# Sound.net
KiCad netlist of a schematic drawn in Altium Designer
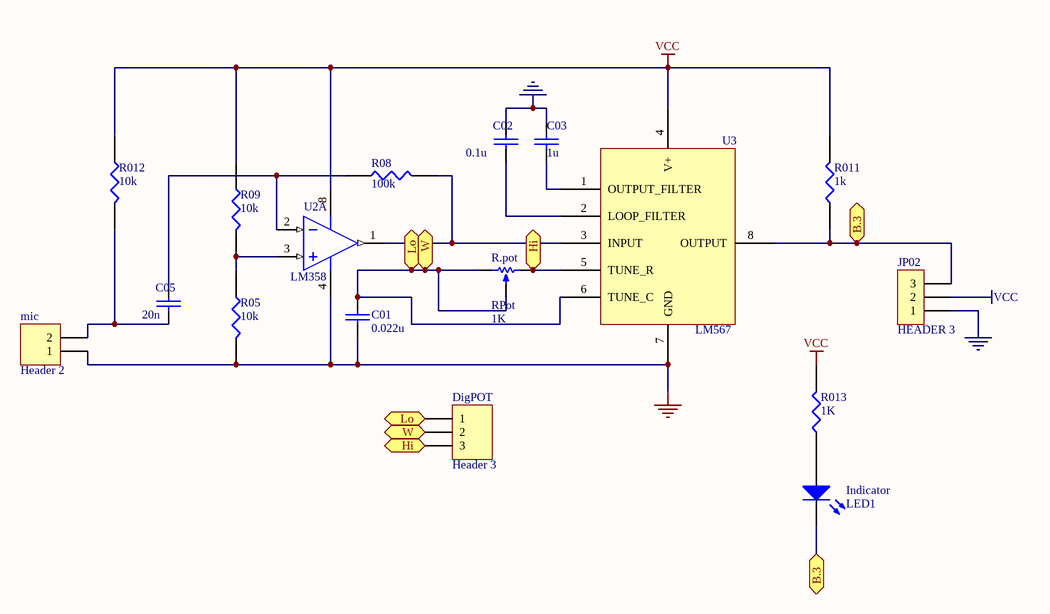
[diagram p0: Sound.SchDoc]

(export (version "E")
  (design (tool "Eeschema 10.0.6"))
  (components
    (comp (ref "C01")
      (value "0.022u")
      (footprint "RAD-0.1")
      (description "Capacitor")
      (libsource (lib "*") (part "CAP"))
    )
    (comp (ref "C02")
      (value "0.1u")
      (footprint "RAD-0.1")
      (description "Capacitor")
      (libsource (lib "*") (part "CAP"))
    )
    (comp (ref "C03")
      (value "1u")
      (footprint "RAD-0.1")
      (description "Capacitor")
      (libsource (lib "*") (part "CAP"))
    )
    (comp (ref "C05")
      (value "20n")
      (footprint "RAD-0.1")
      (description "Capacitor")
      (libsource (lib "*") (part "CAP"))
    )
    (comp (ref "DigPOT")
      (value "Header 3")
      (footprint "HDR1X3")
      (description "Header, 3-Pin")
      (fields (field (name "PUBLISHER") "Altium Limited"))
      (libsource (lib "Miscellaneous Connectors") (part "Header 3"))
    )
    (comp (ref "Indicator")
      (value "LED1")
      (footprint "LED-1")
      (description "Typical RED GaAs LED")
      (fields (field (name "PUBLISHER") "Altium Limited"))
      (libsource (lib "Miscellaneous Devices") (part "LED1"))
    )
    (comp (ref "JP02")
      (value "HEADER 3")
      (footprint "HDR1X3")
      (description "Connector")
      (libsource (lib "*") (part "CON3"))
    )
    (comp (ref "mic")
      (value "Header 2")
      (footprint "HDR1X2")
      (description "Header, 2-Pin")
      (fields (field (name "PUBLISHER") "Altium Limited"))
      (libsource (lib "Miscellaneous Connectors") (part "Header 2"))
    )
    (comp (ref "R.pot")
      (value "RPot")
      (footprint "VR5")
      (description "Potentiometer")
      (fields (field (name "ALTIUM_VALUE") "1K") (field (name "PUBLISHER") "Altium Limited"))
      (libsource (lib "Miscellaneous Devices") (part "RPot"))
    )
    (comp (ref "R05") (value "10k") (footprint "AXIAL-0.3") (libsource (lib "*") (part "RES1")))
    (comp (ref "R08") (value "100k") (footprint "AXIAL-0.3") (libsource (lib "*") (part "RES1")))
    (comp (ref "R09") (value "10k") (footprint "AXIAL-0.3") (libsource (lib "*") (part "RES1")))
    (comp (ref "R011") (value "1k") (footprint "AXIAL-0.3") (libsource (lib "*") (part "RES1")))
    (comp (ref "R012") (value "10k") (footprint "AXIAL-0.3") (libsource (lib "*") (part "RES1")))
    (comp (ref "R013") (value "1K") (footprint "AXIAL-0.3") (libsource (lib "*") (part "RES1")))
    (comp (ref "U2")
      (value "LM358")
      (footprint "DIP-8")
      (description "Fast Settling Dual Operational Amplifier")
      (libsource (lib "*") (part "LM358"))
    )
    (comp (ref "U3") (value "LM567") (footprint "DIP-8") (libsource (lib "*") (part "LM567")))
  )
  (nets
    (net (code "1") (name "/B.3") (class "Default")
      (node (ref "Indicator") (pin "2") (pinfunction "K_2") (pintype "passive"))
      (node (ref "JP02") (pin "3") (pinfunction "3_3") (pintype "passive"))
      (node (ref "R011") (pin "1") (pinfunction "1_1") (pintype "passive"))
      (node (ref "U3") (pin "8") (pinfunction "OUTPUT_8") (pintype "passive"))
    )
    (net (code "2") (name "/Hi") (class "Default")
      (node (ref "DigPOT") (pin "3") (pinfunction "3_3") (pintype "passive"))
      (node (ref "R.pot") (pin "2") (pinfunction "BOT_2") (pintype "passive"))
      (node (ref "U3") (pin "5") (pinfunction "TUNE_R_5") (pintype "passive"))
    )
    (net (code "3") (name "/Lo") (class "Default")
      (node (ref "C01") (pin "1") (pinfunction "1_1") (pintype "passive"))
      (node (ref "DigPOT") (pin "1") (pinfunction "1_1") (pintype "passive"))
      (node (ref "DigPOT") (pin "2") (pinfunction "2_2") (pintype "passive"))
      (node (ref "R.pot") (pin "1") (pinfunction "TOP_1") (pintype "passive"))
      (node (ref "R.pot") (pin "3") (pinfunction "TAP_3") (pintype "passive"))
      (node (ref "U3") (pin "6") (pinfunction "TUNE_C_6") (pintype "passive"))
    )
    (net (code "4") (name "GND") (class "Default")
      (node (ref "C01") (pin "2") (pinfunction "2_2") (pintype "passive"))
      (node (ref "C02") (pin "1") (pinfunction "1_1") (pintype "passive"))
      (node (ref "C03") (pin "1") (pinfunction "1_1") (pintype "passive"))
      (node (ref "JP02") (pin "1") (pinfunction "1_1") (pintype "passive"))
      (node (ref "R05") (pin "2") (pinfunction "2_2") (pintype "passive"))
      (node (ref "U2") (pin "4") (pinfunction "V-_4") (pintype "power_in"))
      (node (ref "U3") (pin "7") (pinfunction "GND_7") (pintype "passive"))
      (node (ref "mic") (pin "1") (pinfunction "1_1") (pintype "passive"))
    )
    (net (code "5") (name "Net-(C05-Pad2)") (class "Default")
      (node (ref "C05") (pin "2") (pinfunction "2_2") (pintype "passive"))
      (node (ref "R012") (pin "2") (pinfunction "2_2") (pintype "passive"))
      (node (ref "mic") (pin "2") (pinfunction "2_2") (pintype "passive"))
    )
    (net (code "6") (name "Net-(Indicator-A)") (class "Default")
      (node (ref "Indicator") (pin "1") (pinfunction "A_1") (pintype "passive"))
      (node (ref "R013") (pin "1") (pinfunction "1_1") (pintype "passive"))
    )
    (net (code "7") (name "Net-(U2A-IN1+)") (class "Default")
      (node (ref "R05") (pin "1") (pinfunction "1_1") (pintype "passive"))
      (node (ref "R09") (pin "2") (pinfunction "2_2") (pintype "passive"))
      (node (ref "U2") (pin "3") (pinfunction "IN1+_3") (pintype "input"))
    )
    (net (code "8") (name "Net-(U2A-IN1-)") (class "Default")
      (node (ref "C05") (pin "1") (pinfunction "1_1") (pintype "passive"))
      (node (ref "R08") (pin "1") (pinfunction "1_1") (pintype "passive"))
      (node (ref "U2") (pin "2") (pinfunction "IN1-_2") (pintype "input"))
    )
    (net (code "9") (name "Net-(U2A-OUT1)") (class "Default")
      (node (ref "R08") (pin "2") (pinfunction "2_2") (pintype "passive"))
      (node (ref "U2") (pin "1") (pinfunction "OUT1_1") (pintype "output"))
      (node (ref "U3") (pin "3") (pinfunction "INPUT_3") (pintype "passive"))
    )
    (net (code "10") (name "Net-(U3-LOOP_FILTER)") (class "Default")
      (node (ref "C02") (pin "2") (pinfunction "2_2") (pintype "passive"))
      (node (ref "U3") (pin "2") (pinfunction "LOOP_FILTER_2") (pintype "passive"))
    )
    (net (code "11") (name "Net-(U3-OUTPUT_FILTER)") (class "Default")
      (node (ref "C03") (pin "2") (pinfunction "2_2") (pintype "passive"))
      (node (ref "U3") (pin "1") (pinfunction "OUTPUT_FILTER_1") (pintype "passive"))
    )
    (net (code "12") (name "VCC") (class "Default")
      (node (ref "JP02") (pin "2") (pinfunction "2_2") (pintype "passive"))
      (node (ref "R011") (pin "2") (pinfunction "2_2") (pintype "passive"))
      (node (ref "R012") (pin "1") (pinfunction "1_1") (pintype "passive"))
      (node (ref "R013") (pin "2") (pinfunction "2_2") (pintype "passive"))
      (node (ref "R09") (pin "1") (pinfunction "1_1") (pintype "passive"))
      (node (ref "U2") (pin "8") (pinfunction "V+_8") (pintype "power_in"))
      (node (ref "U3") (pin "4") (pinfunction "V+_4") (pintype "passive"))
    )
  )
)
